# GATE_DRIVER.net
KiCad netlist of a schematic drawn in Altium Designer
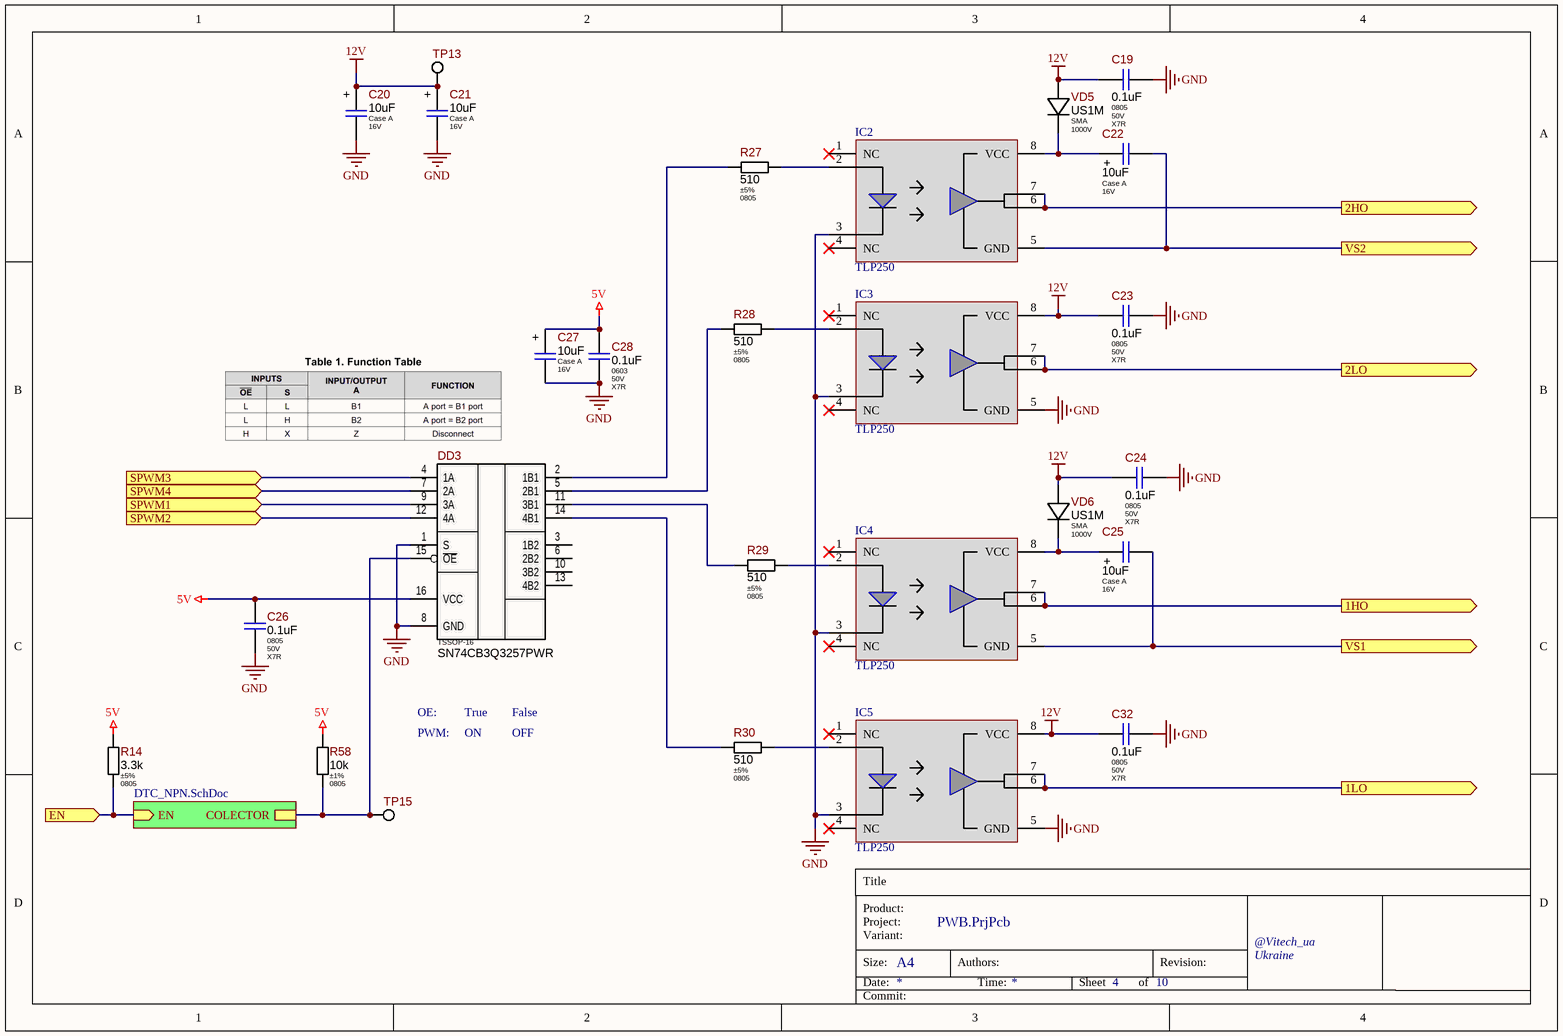
[diagram p0: GATE_DRIVER.SchDoc]

(export (version "E")
  (design (tool "Eeschema 10.0.6"))
  (components
    (comp (ref "C19")
      (value "0.1uF")
      (footprint "CAP-0805(2012)X85T10")
      (description "100nF 50V X7R ±10% 0805 Ceramic Capacitor RoHS")
      (fields
        (field (name "PACKAGE") "0805")
        (field (name "VOLTAGE") "50V")
        (field (name "DIELECTRIC TYPE") "X7R")
        (field (name "PART NUMBER") "CL21B104KBCNNNC")
        (field (name "MANUFACTURER") "Samsung Electro-Mechanics")
      )
      (libsource (lib "capacitors") (part "CL21B104KBCNNNC"))
    )
    (comp (ref "C20")
      (value "10uF")
      (footprint "C_TANTAL_CASE_A_MED")
      (description "10uF 16V ±10% Case A Tantalum Capacitors, 3Ohm")
      (fields
        (field (name "PACKAGE") "Case A")
        (field (name "VOLTAGE") "16V")
        (field (name "PART NUMBER") "TAJA106K016RNJ")
        (field (name "MANUFACTURER") "AVX")
      )
      (libsource (lib "capacitors") (part "TAJA106K016RNJ"))
    )
    (comp (ref "C21")
      (value "10uF")
      (footprint "C_TANTAL_CASE_A_MED")
      (description "10uF 16V ±10% Case A Tantalum Capacitors, 3Ohm")
      (fields
        (field (name "PACKAGE") "Case A")
        (field (name "VOLTAGE") "16V")
        (field (name "PART NUMBER") "TAJA106K016RNJ")
        (field (name "MANUFACTURER") "AVX")
      )
      (libsource (lib "capacitors") (part "TAJA106K016RNJ"))
    )
    (comp (ref "C22")
      (value "10uF")
      (footprint "C_TANTAL_CASE_A_MED")
      (description "10uF 16V ±10% Case A Tantalum Capacitors, 3Ohm")
      (fields
        (field (name "PACKAGE") "Case A")
        (field (name "VOLTAGE") "16V")
        (field (name "PART NUMBER") "TAJA106K016RNJ")
        (field (name "MANUFACTURER") "AVX")
      )
      (libsource (lib "capacitors") (part "TAJA106K016RNJ"))
    )
    (comp (ref "C23")
      (value "0.1uF")
      (footprint "CAP-0805(2012)X85T10")
      (description "100nF 50V X7R ±10% 0805 Ceramic Capacitor RoHS")
      (fields
        (field (name "PACKAGE") "0805")
        (field (name "VOLTAGE") "50V")
        (field (name "DIELECTRIC TYPE") "X7R")
        (field (name "PART NUMBER") "CL21B104KBCNNNC")
        (field (name "MANUFACTURER") "Samsung Electro-Mechanics")
      )
      (libsource (lib "capacitors") (part "CL21B104KBCNNNC"))
    )
    (comp (ref "C24")
      (value "0.1uF")
      (footprint "CAP-0805(2012)X85T10")
      (description "100nF 50V X7R ±10% 0805 Ceramic Capacitor RoHS")
      (fields
        (field (name "PACKAGE") "0805")
        (field (name "VOLTAGE") "50V")
        (field (name "DIELECTRIC TYPE") "X7R")
        (field (name "PART NUMBER") "CL21B104KBCNNNC")
        (field (name "MANUFACTURER") "Samsung Electro-Mechanics")
      )
      (libsource (lib "capacitors") (part "CL21B104KBCNNNC"))
    )
    (comp (ref "C25")
      (value "10uF")
      (footprint "C_TANTAL_CASE_A_MED")
      (description "10uF 16V ±10% Case A Tantalum Capacitors, 3Ohm")
      (fields
        (field (name "PACKAGE") "Case A")
        (field (name "VOLTAGE") "16V")
        (field (name "PART NUMBER") "TAJA106K016RNJ")
        (field (name "MANUFACTURER") "AVX")
      )
      (libsource (lib "capacitors") (part "TAJA106K016RNJ"))
    )
    (comp (ref "C26")
      (value "0.1uF")
      (footprint "CAP-0805(2012)X85T10")
      (description "100nF 50V X7R ±10% 0805 Ceramic Capacitor RoHS")
      (fields
        (field (name "PACKAGE") "0805")
        (field (name "VOLTAGE") "50V")
        (field (name "DIELECTRIC TYPE") "X7R")
        (field (name "PART NUMBER") "CL21B104KBCNNNC")
        (field (name "MANUFACTURER") "Samsung Electro-Mechanics")
      )
      (libsource (lib "capacitors") (part "CL21B104KBCNNNC"))
    )
    (comp (ref "C27")
      (value "10uF")
      (footprint "C_TANTAL_CASE_A_MED")
      (description "10uF 16V ±10% Case A Tantalum Capacitors, 3Ohm")
      (fields
        (field (name "PACKAGE") "Case A")
        (field (name "VOLTAGE") "16V")
        (field (name "PART NUMBER") "TAJA106K016RNJ")
        (field (name "MANUFACTURER") "AVX")
      )
      (libsource (lib "capacitors") (part "TAJA106K016RNJ"))
    )
    (comp (ref "C28")
      (value "0.1uF")
      (footprint "C_CERAMIC_0603_MED")
      (description "100nF 50V X7R ±10% 0603 Ceramic Capacitor RoHS")
      (fields
        (field (name "PACKAGE") "0603")
        (field (name "VOLTAGE") "50V")
        (field (name "DIELECTRIC TYPE") "X7R")
        (field (name "PART NUMBER") "CL10B104KB8NNND")
        (field (name "MANUFACTURER") "Samsung Electro-Mechanics")
      )
      (libsource (lib "capacitors") (part "CL10B104KB8NNND"))
    )
    (comp (ref "C32")
      (value "0.1uF")
      (footprint "CAP-0805(2012)X85T10")
      (description "100nF 50V X7R ±10% 0805 Ceramic Capacitor RoHS")
      (fields
        (field (name "PACKAGE") "0805")
        (field (name "VOLTAGE") "50V")
        (field (name "DIELECTRIC TYPE") "X7R")
        (field (name "PART NUMBER") "CL21B104KBCNNNC")
        (field (name "MANUFACTURER") "Samsung Electro-Mechanics")
      )
      (libsource (lib "capacitors") (part "CL21B104KBCNNNC"))
    )
    (comp (ref "DD3")
      (value "SN74CB3Q3257PWR")
      (footprint "TSSOP-16")
      (description "4-Bit 1-of-2 FET Multiplexer/Demultiplexer 2.5V/3.3V Low-Voltage High-Bandwidth Bus Switch")
      (fields
        (field (name "PACKAGE") "TSSOP-16")
        (field (name "PART NUMBER") "SN74CB3Q3257PWR")
        (field (name "MANUFACTURER") "Texas Instruments")
      )
      (libsource (lib "ic") (part "SN74CB3Q3257PWR"))
    )
    (comp (ref "IC2")
      (value "TLP250")
      (footprint "DIP762W60P254L966H485Q8N")
      (description "Integrated Circuit")
      (fields
        (field (name "MANUFACTURER_PART_NUMBER") "TLP250(F)")
        (field (name "MOUSER PART NUMBER") "757-TLP250(F)")
      )
      (libsource (lib "vitech_lib") (part "TLP250"))
    )
    (comp (ref "IC3")
      (value "TLP250")
      (footprint "DIP762W60P254L966H485Q8N")
      (description "Integrated Circuit")
      (fields
        (field (name "MANUFACTURER_PART_NUMBER") "TLP250(F)")
        (field (name "MOUSER PART NUMBER") "757-TLP250(F)")
      )
      (libsource (lib "vitech_lib") (part "TLP250"))
    )
    (comp (ref "IC4")
      (value "TLP250")
      (footprint "DIP762W60P254L966H485Q8N")
      (description "Integrated Circuit")
      (fields
        (field (name "MANUFACTURER_PART_NUMBER") "TLP250(F)")
        (field (name "MOUSER PART NUMBER") "757-TLP250(F)")
      )
      (libsource (lib "vitech_lib") (part "TLP250"))
    )
    (comp (ref "IC5")
      (value "TLP250")
      (footprint "DIP762W60P254L966H485Q8N")
      (description "Integrated Circuit")
      (fields
        (field (name "MANUFACTURER_PART_NUMBER") "TLP250(F)")
        (field (name "MOUSER PART NUMBER") "757-TLP250(F)")
      )
      (libsource (lib "vitech_lib") (part "TLP250"))
    )
    (comp (ref "R14")
      (value "3.3k")
      (footprint "R_ANY_CHIP_0805_MED")
      (description "3.3 kOhms ±5%, 1/8W 0805 Thick Film Resistor")
      (fields
        (field (name "TOLERANCE") "±5%")
        (field (name "PACKAGE") "0805")
        (field (name "PART NUMBER") "RC0805JR-073K3L")
        (field (name "MANUFACTURER") "Yageo")
      )
      (libsource (lib "resistors") (part "RC0805JR-073K3L"))
    )
    (comp (ref "R27")
      (value "510")
      (footprint "R_ANY_CHIP_0805_MED")
      (description "510 Ohms ±5%, 1/8W 0805 Thick Film Resistor")
      (fields
        (field (name "TOLERANCE") "±5%")
        (field (name "PACKAGE") "0805")
        (field (name "PART NUMBER") "CRCW0805510RJNEA")
        (field (name "MANUFACTURER") "Vishay")
      )
      (libsource (lib "resistors") (part "CRCW0805510RJNEA"))
    )
    (comp (ref "R28")
      (value "510")
      (footprint "R_ANY_CHIP_0805_MED")
      (description "510 Ohms ±5%, 1/8W 0805 Thick Film Resistor")
      (fields
        (field (name "TOLERANCE") "±5%")
        (field (name "PACKAGE") "0805")
        (field (name "PART NUMBER") "CRCW0805510RJNEA")
        (field (name "MANUFACTURER") "Vishay")
      )
      (libsource (lib "resistors") (part "CRCW0805510RJNEA"))
    )
    (comp (ref "R29")
      (value "510")
      (footprint "R_ANY_CHIP_0805_MED")
      (description "510 Ohms ±5%, 1/8W 0805 Thick Film Resistor")
      (fields
        (field (name "TOLERANCE") "±5%")
        (field (name "PACKAGE") "0805")
        (field (name "PART NUMBER") "CRCW0805510RJNEA")
        (field (name "MANUFACTURER") "Vishay")
      )
      (libsource (lib "resistors") (part "CRCW0805510RJNEA"))
    )
    (comp (ref "R30")
      (value "510")
      (footprint "R_ANY_CHIP_0805_MED")
      (description "510 Ohms ±5%, 1/8W 0805 Thick Film Resistor")
      (fields
        (field (name "TOLERANCE") "±5%")
        (field (name "PACKAGE") "0805")
        (field (name "PART NUMBER") "CRCW0805510RJNEA")
        (field (name "MANUFACTURER") "Vishay")
      )
      (libsource (lib "resistors") (part "CRCW0805510RJNEA"))
    )
    (comp (ref "R58")
      (value "10k")
      (footprint "R_ANY_CHIP_0805_MED")
      (description "10 kOhms ±1%, 1/8W 0805 Thick Film Resistor")
      (fields
        (field (name "TOLERANCE") "±1%")
        (field (name "PACKAGE") "0805")
        (field (name "PART NUMBER") "RC0805FR-0710K2L")
        (field (name "MANUFACTURER") "Yageo")
      )
      (libsource (lib "resistors") (part "RC0805FR-0710K2L"))
    )
    (comp (ref "TP13")
      (value "PAD-0.96mm")
      (footprint "PAD-0.96mm")
      (description "0.96mm Pad for Plug-In or Receptacle")
      (fields (field (name "MANUFACTURER") "NONE"))
      (libsource (lib "probetools") (part "PAD-0.96mm"))
    )
    (comp (ref "TP15")
      (value "PAD-0.96mm")
      (footprint "PAD-0.96mm")
      (description "0.96mm Pad for Plug-In or Receptacle")
      (fields (field (name "MANUFACTURER") "NONE"))
      (libsource (lib "probetools") (part "PAD-0.96mm"))
    )
    (comp (ref "VD5")
      (value "US1M")
      (footprint "SMA_MED")
      (description "Diode Standard 1000V 1A, 75ns, SMA")
      (fields
        (field (name "PART NUMBER") "US1M")
        (field (name "PACKAGE") "SMA")
        (field (name "VOLTAGE") "1000V")
        (field (name "MANUFACTURER") "Diodec Semiconductor")
      )
      (libsource (lib "diodes") (part "US1M"))
    )
    (comp (ref "VD6")
      (value "US1M")
      (footprint "SMA_MED")
      (description "Diode Standard 1000V 1A, 75ns, SMA")
      (fields
        (field (name "PART NUMBER") "US1M")
        (field (name "PACKAGE") "SMA")
        (field (name "VOLTAGE") "1000V")
        (field (name "MANUFACTURER") "Diodec Semiconductor")
      )
      (libsource (lib "diodes") (part "US1M"))
    )
  )
  (nets
    (net (code "1") (name "/1HO") (class "Default")
      (node (ref "IC4") (pin "6") (pinfunction "VO_(OUTPUT)_6") (pintype "passive"))
      (node (ref "IC4") (pin "7") (pinfunction "VO_7") (pintype "passive"))
    )
    (net (code "2") (name "/1LO") (class "Default")
      (node (ref "IC5") (pin "6") (pinfunction "VO_(OUTPUT)_6") (pintype "passive"))
      (node (ref "IC5") (pin "7") (pinfunction "VO_7") (pintype "passive"))
    )
    (net (code "3") (name "/2HO") (class "Default")
      (node (ref "IC2") (pin "6") (pinfunction "VO_(OUTPUT)_6") (pintype "passive"))
      (node (ref "IC2") (pin "7") (pinfunction "VO_7") (pintype "passive"))
    )
    (net (code "4") (name "/2LO") (class "Default")
      (node (ref "IC3") (pin "6") (pinfunction "VO_(OUTPUT)_6") (pintype "passive"))
      (node (ref "IC3") (pin "7") (pinfunction "VO_7") (pintype "passive"))
    )
    (net (code "5") (name "/COLECTOR") (class "Default")
      (node (ref "DD3") (pin "15") (pinfunction "~{OE}_15") (pintype "passive"))
      (node (ref "R58") (pin "1") (pintype "passive"))
      (node (ref "TP15") (pin "1") (pintype "passive"))
    )
    (net (code "6") (name "/EN") (class "Default") (node (ref "R14") (pin "2") (pintype "passive")))
    (net (code "7") (name "/SPWM1") (class "Default")
      (node (ref "DD3") (pin "9") (pinfunction "3A_9") (pintype "passive"))
    )
    (net (code "8") (name "/SPWM2") (class "Default")
      (node (ref "DD3") (pin "12") (pinfunction "4A_12") (pintype "passive"))
    )
    (net (code "9") (name "/SPWM3") (class "Default")
      (node (ref "DD3") (pin "4") (pinfunction "1A_4") (pintype "passive"))
    )
    (net (code "10") (name "/SPWM4") (class "Default")
      (node (ref "DD3") (pin "7") (pinfunction "2A_7") (pintype "passive"))
    )
    (net (code "11") (name "/VS1") (class "Default")
      (node (ref "C25") (pin "2") (pinfunction "2_2") (pintype "passive"))
      (node (ref "IC4") (pin "5") (pinfunction "GND_5") (pintype "passive"))
    )
    (net (code "12") (name "/VS2") (class "Default")
      (node (ref "C22") (pin "2") (pinfunction "2_2") (pintype "passive"))
      (node (ref "IC2") (pin "5") (pinfunction "GND_5") (pintype "passive"))
    )
    (net (code "13") (name "5V") (class "Default")
      (node (ref "C26") (pin "1") (pinfunction "1_1") (pintype "passive"))
      (node (ref "C27") (pin "1") (pinfunction "1_1") (pintype "passive"))
      (node (ref "C28") (pin "2") (pinfunction "2_2") (pintype "passive"))
      (node (ref "DD3") (pin "16") (pinfunction "VCC_16") (pintype "passive"))
      (node (ref "R14") (pin "1") (pintype "passive"))
      (node (ref "R58") (pin "2") (pintype "passive"))
    )
    (net (code "14") (name "12V") (class "Default")
      (node (ref "C19") (pin "1") (pinfunction "1_1") (pintype "passive"))
      (node (ref "C20") (pin "1") (pinfunction "1_1") (pintype "passive"))
      (node (ref "C21") (pin "1") (pinfunction "1_1") (pintype "passive"))
      (node (ref "C23") (pin "1") (pinfunction "1_1") (pintype "passive"))
      (node (ref "C24") (pin "1") (pinfunction "1_1") (pintype "passive"))
      (node (ref "C32") (pin "1") (pinfunction "1_1") (pintype "passive"))
      (node (ref "IC3") (pin "8") (pinfunction "VCC_8") (pintype "passive"))
      (node (ref "IC5") (pin "8") (pinfunction "VCC_8") (pintype "passive"))
      (node (ref "TP13") (pin "1") (pintype "passive"))
      (node (ref "VD5") (pin "AN") (pintype "passive"))
      (node (ref "VD6") (pin "AN") (pintype "passive"))
    )
    (net (code "15") (name "GND") (class "Default")
      (node (ref "C19") (pin "2") (pinfunction "2_2") (pintype "passive"))
      (node (ref "C20") (pin "2") (pinfunction "2_2") (pintype "passive"))
      (node (ref "C21") (pin "2") (pinfunction "2_2") (pintype "passive"))
      (node (ref "C23") (pin "2") (pinfunction "2_2") (pintype "passive"))
      (node (ref "C24") (pin "2") (pinfunction "2_2") (pintype "passive"))
      (node (ref "C26") (pin "2") (pinfunction "2_2") (pintype "passive"))
      (node (ref "C27") (pin "2") (pinfunction "2_2") (pintype "passive"))
      (node (ref "C28") (pin "1") (pinfunction "1_1") (pintype "passive"))
      (node (ref "C32") (pin "2") (pinfunction "2_2") (pintype "passive"))
      (node (ref "DD3") (pin "1") (pinfunction "S_1") (pintype "passive"))
      (node (ref "DD3") (pin "8") (pinfunction "GND_8") (pintype "passive"))
      (node (ref "IC2") (pin "3") (pinfunction "C_3") (pintype "passive"))
      (node (ref "IC3") (pin "3") (pinfunction "C_3") (pintype "passive"))
      (node (ref "IC3") (pin "5") (pinfunction "GND_5") (pintype "passive"))
      (node (ref "IC4") (pin "3") (pinfunction "C_3") (pintype "passive"))
      (node (ref "IC5") (pin "3") (pinfunction "C_3") (pintype "passive"))
      (node (ref "IC5") (pin "5") (pinfunction "GND_5") (pintype "passive"))
    )
    (net (code "16") (name "Net-(DD3-1B1)") (class "Default")
      (node (ref "DD3") (pin "2") (pinfunction "1B1_2") (pintype "passive"))
      (node (ref "R27") (pin "1") (pintype "passive"))
    )
    (net (code "17") (name "Net-(DD3-2B1)") (class "Default")
      (node (ref "DD3") (pin "5") (pinfunction "2B1_5") (pintype "passive"))
      (node (ref "R28") (pin "1") (pintype "passive"))
    )
    (net (code "18") (name "Net-(DD3-3B1)") (class "Default")
      (node (ref "DD3") (pin "11") (pinfunction "3B1_11") (pintype "passive"))
      (node (ref "R29") (pin "1") (pintype "passive"))
    )
    (net (code "19") (name "Net-(DD3-4B1)") (class "Default")
      (node (ref "DD3") (pin "14") (pinfunction "4B1_14") (pintype "passive"))
      (node (ref "R30") (pin "1") (pintype "passive"))
    )
    (net (code "20") (name "Net-(IC2-A)") (class "Default")
      (node (ref "IC2") (pin "2") (pinfunction "A_2") (pintype "passive"))
      (node (ref "R27") (pin "2") (pintype "passive"))
    )
    (net (code "21") (name "Net-(IC2-VCC)") (class "Default")
      (node (ref "C22") (pin "1") (pinfunction "1_1") (pintype "passive"))
      (node (ref "IC2") (pin "8") (pinfunction "VCC_8") (pintype "passive"))
      (node (ref "VD5") (pin "CA") (pintype "passive"))
    )
    (net (code "22") (name "Net-(IC3-A)") (class "Default")
      (node (ref "IC3") (pin "2") (pinfunction "A_2") (pintype "passive"))
      (node (ref "R28") (pin "2") (pintype "passive"))
    )
    (net (code "23") (name "Net-(IC4-A)") (class "Default")
      (node (ref "IC4") (pin "2") (pinfunction "A_2") (pintype "passive"))
      (node (ref "R29") (pin "2") (pintype "passive"))
    )
    (net (code "24") (name "Net-(IC4-VCC)") (class "Default")
      (node (ref "C25") (pin "1") (pinfunction "1_1") (pintype "passive"))
      (node (ref "IC4") (pin "8") (pinfunction "VCC_8") (pintype "passive"))
      (node (ref "VD6") (pin "CA") (pintype "passive"))
    )
    (net (code "25") (name "Net-(IC5-A)") (class "Default")
      (node (ref "IC5") (pin "2") (pinfunction "A_2") (pintype "passive"))
      (node (ref "R30") (pin "2") (pintype "passive"))
    )
    (net (code "26") (name "unconnected-(DD3-1B2-Pad3)") (class "Default")
      (node (ref "DD3") (pin "3") (pinfunction "1B2_3") (pintype "passive"))
    )
    (net (code "27") (name "unconnected-(DD3-2B2-Pad6)") (class "Default")
      (node (ref "DD3") (pin "6") (pinfunction "2B2_6") (pintype "passive"))
    )
    (net (code "28") (name "unconnected-(DD3-3B2-Pad10)") (class "Default")
      (node (ref "DD3") (pin "10") (pinfunction "3B2_10") (pintype "passive"))
    )
    (net (code "29") (name "unconnected-(DD3-4B2-Pad13)") (class "Default")
      (node (ref "DD3") (pin "13") (pinfunction "4B2_13") (pintype "passive"))
    )
    (net (code "30") (name "unconnected-(IC2-NC-Pad1)") (class "Default")
      (node (ref "IC2") (pin "1") (pinfunction "NC_1") (pintype "passive+no_connect"))
    )
    (net (code "31") (name "unconnected-(IC2-NC-Pad4)") (class "Default")
      (node (ref "IC2") (pin "4") (pinfunction "NC_4") (pintype "passive+no_connect"))
    )
    (net (code "32") (name "unconnected-(IC3-NC-Pad1)") (class "Default")
      (node (ref "IC3") (pin "1") (pinfunction "NC_1") (pintype "passive+no_connect"))
    )
    (net (code "33") (name "unconnected-(IC3-NC-Pad4)") (class "Default")
      (node (ref "IC3") (pin "4") (pinfunction "NC_4") (pintype "passive+no_connect"))
    )
    (net (code "34") (name "unconnected-(IC4-NC-Pad1)") (class "Default")
      (node (ref "IC4") (pin "1") (pinfunction "NC_1") (pintype "passive+no_connect"))
    )
    (net (code "35") (name "unconnected-(IC4-NC-Pad4)") (class "Default")
      (node (ref "IC4") (pin "4") (pinfunction "NC_4") (pintype "passive+no_connect"))
    )
    (net (code "36") (name "unconnected-(IC5-NC-Pad1)") (class "Default")
      (node (ref "IC5") (pin "1") (pinfunction "NC_1") (pintype "passive+no_connect"))
    )
    (net (code "37") (name "unconnected-(IC5-NC-Pad4)") (class "Default")
      (node (ref "IC5") (pin "4") (pinfunction "NC_4") (pintype "passive+no_connect"))
    )
  )
)
